# Sheet1.net
KiCad netlist of a schematic drawn in Altium Designer
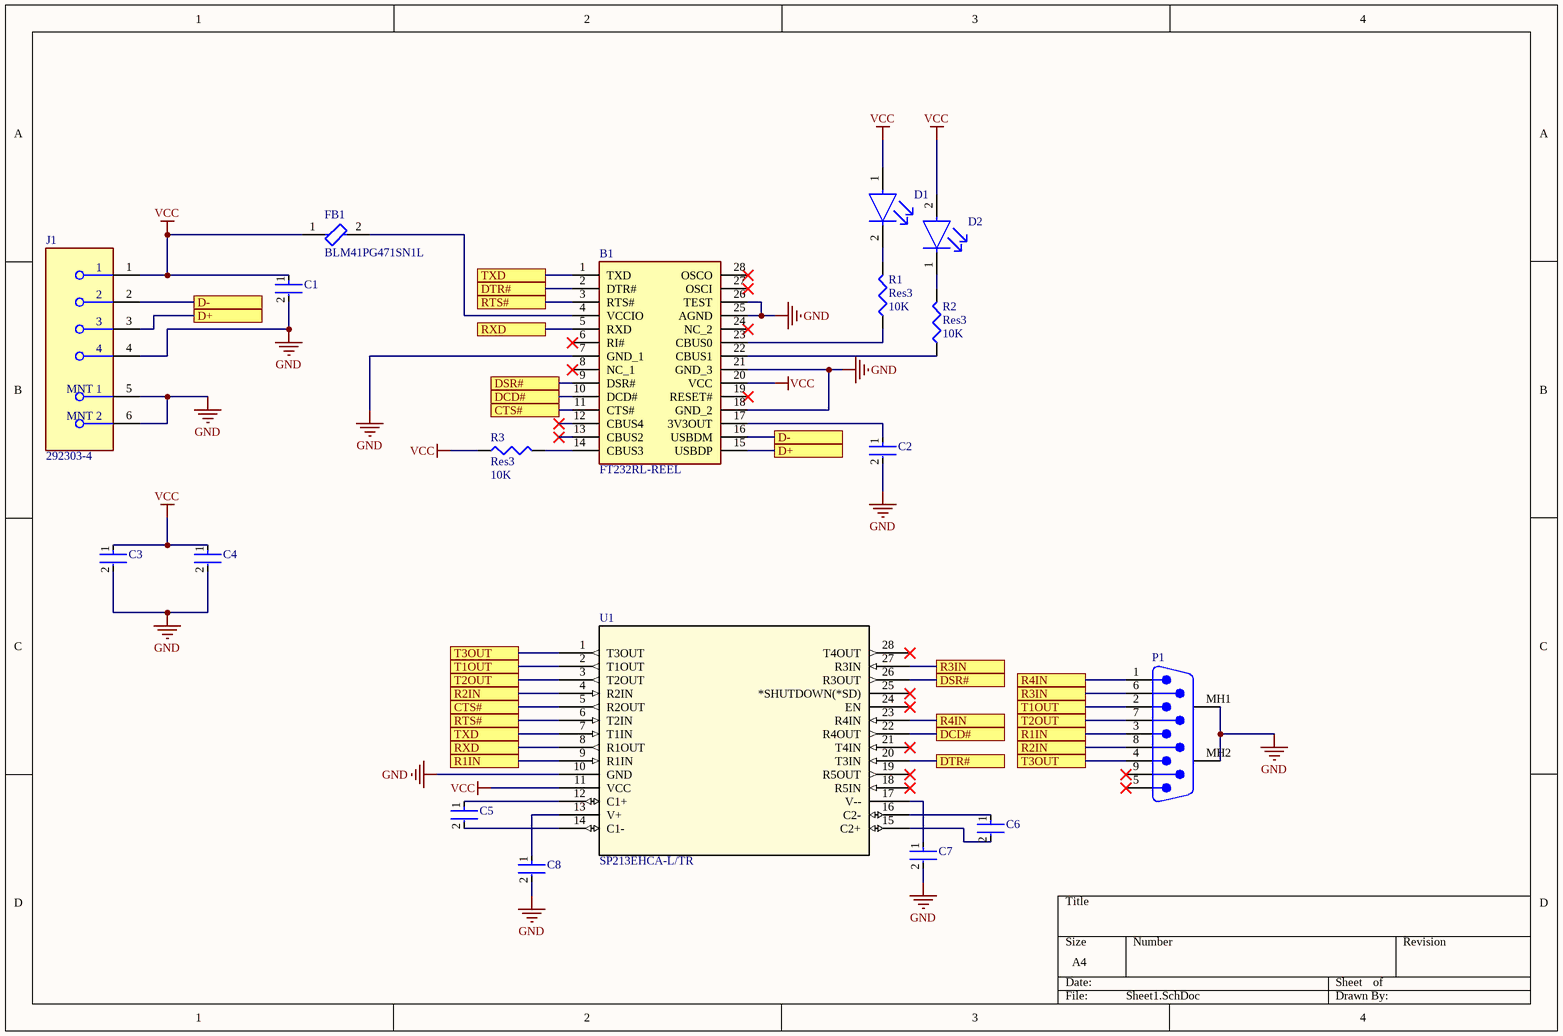
[diagram p0: Sheet1.SchDoc]

(export (version "E")
  (design (tool "Eeschema 10.0.6"))
  (components
    (comp (ref "B1")
      (value "FT232RL-REEL")
      (footprint "SOP65P780X200-28N")
      (description "USB Bridge, USB to UART USB 2.0 UART Interface 28-SSOP")
      (libsource (lib "FT232RL-REEL") (part "FT232RL-REEL"))
    )
    (comp (ref "C1")
      (value "CC0402KPX7R6BB104")
      (footprint "FP-CC0402-MFG")
      (description "CC0402 100 nF X7R 10.00% 10 V")
      (fields
        (field (name "OCTOPART") "https://octopart.com/cc0402kpx7r6bb104-yageo-12885101")
        (field (name "TOLERANCE") "0.1")
      )
      (libsource (lib "Altium Content Vault") (part "11868f565c42a9108669ba33697ecf6"))
    )
    (comp (ref "C2")
      (value "C0603C104M3VAC")
      (footprint "FP-C0603C-CF-MFG")
      (description "C0603 0.10 μF Y5V 30ppm/°C 20.00% 25 V")
      (fields
        (field (name "OCTOPART") "https://octopart.com/c0603c104m3vac-kemet-1325404")
        (field (name "MANUFACTURER") "KEMET")
      )
      (libsource (lib "Altium Content Vault") (part "b4654b650e69147ec39a6b967a45e02"))
    )
    (comp (ref "C3")
      (value "C0603C104M3VAC")
      (footprint "FP-C0603C-CF-MFG")
      (description "C0603 0.10 μF Y5V 30ppm/°C 20.00% 25 V")
      (fields
        (field (name "OCTOPART") "https://octopart.com/c0603c104m3vac-kemet-1325404")
        (field (name "MANUFACTURER") "KEMET")
      )
      (libsource (lib "Altium Content Vault") (part "b4654b650e69147ec39a6b967a45e02"))
    )
    (comp (ref "C4")
      (value "C0603C104M3VAC")
      (footprint "FP-C0603C-CF-MFG")
      (description "C0603 0.10 μF Y5V 30ppm/°C 20.00% 25 V")
      (fields
        (field (name "OCTOPART") "https://octopart.com/c0603c104m3vac-kemet-1325404")
        (field (name "MANUFACTURER") "KEMET")
      )
      (libsource (lib "Altium Content Vault") (part "b4654b650e69147ec39a6b967a45e02"))
    )
    (comp (ref "C5")
      (value "C0603C104M3VAC")
      (footprint "FP-C0603C-CF-MFG")
      (description "C0603 0.10 μF Y5V 30ppm/°C 20.00% 25 V")
      (fields
        (field (name "OCTOPART") "https://octopart.com/c0603c104m3vac-kemet-1325404")
        (field (name "MANUFACTURER") "KEMET")
      )
      (libsource (lib "Altium Content Vault") (part "b4654b650e69147ec39a6b967a45e02"))
    )
    (comp (ref "C6")
      (value "C0603C104M3VAC")
      (footprint "FP-C0603C-CF-MFG")
      (description "C0603 0.10 μF Y5V 30ppm/°C 20.00% 25 V")
      (fields
        (field (name "OCTOPART") "https://octopart.com/c0603c104m3vac-kemet-1325404")
        (field (name "MANUFACTURER") "KEMET")
      )
      (libsource (lib "Altium Content Vault") (part "b4654b650e69147ec39a6b967a45e02"))
    )
    (comp (ref "C7")
      (value "C0603C104M3VAC")
      (footprint "FP-C0603C-CF-MFG")
      (description "C0603 0.10 μF Y5V 30ppm/°C 20.00% 25 V")
      (fields
        (field (name "OCTOPART") "https://octopart.com/c0603c104m3vac-kemet-1325404")
        (field (name "MANUFACTURER") "KEMET")
      )
      (libsource (lib "Altium Content Vault") (part "b4654b650e69147ec39a6b967a45e02"))
    )
    (comp (ref "C8")
      (value "C0603C104M3VAC")
      (footprint "FP-C0603C-CF-MFG")
      (description "C0603 0.10 μF Y5V 30ppm/°C 20.00% 25 V")
      (fields
        (field (name "OCTOPART") "https://octopart.com/c0603c104m3vac-kemet-1325404")
        (field (name "MANUFACTURER") "KEMET")
      )
      (libsource (lib "Altium Content Vault") (part "b4654b650e69147ec39a6b967a45e02"))
    )
    (comp (ref "D1")
      (value "AP2012EC")
      (footprint "FP-AP2012EC-MFG")
      (description "LED RED CLEAR SMD")
      (libsource (lib "Altium Content Vault") (part "ab1c01a81903e929fc6c44469aada92"))
    )
    (comp (ref "D2")
      (value "APT1608LZGCK")
      (footprint "FP-APT1608LZGCK-MFG")
      (description "LED GREEN CLEAR 2SMD")
      (libsource (lib "Altium Content Vault") (part "8706943c75ba83719d021d2fdc84c58"))
    )
    (comp (ref "FB1")
      (value "BLM41PG471SN1L")
      (footprint "FP-BLM41-0_2-a1_2-IPC_B")
      (description "Ferrite Bead, 1806, 470Ω @ 100MHz, 25%, 0.05Ω, 2A")
      (fields (field (name "TOLERANCE") "25%"))
      (libsource (lib "Altium Content Vault") (part "5f30dd21d616792df468990f7003faa"))
    )
    (comp (ref "J1")
      (value "292303-4")
      (footprint "FP-292303-4-MFG")
      (description "CONN RCPT USB2.0 TYPEA 4POS R/A")
      (fields
        (field (name "MANUFACTURER") "TE Connectivity")
        (field (name "OCTOPART") "https://octopart.com/292303-4-te+connectivity-39545343")
      )
      (libsource (lib "Altium Content Vault") (part "79e6714efa0bb2f851c24b2688127c9"))
    )
    (comp (ref "P1")
      (value "5747840-3")
      (footprint "TECO-5747840-3_V")
      (fields (field (name "MANUFACTURER") "TE Connectivity"))
      (libsource (lib "Altium Content Vault") (part "CN-2S-2M-D9"))
    )
    (comp (ref "R1")
      (value "Res3")
      (footprint "J1-0603")
      (description "Resistor")
      (fields (field (name "ALTIUM_VALUE") "10K") (field (name "PUBLISHER") "Altium Limited"))
      (libsource (lib "Miscellaneous Devices") (part "Res3"))
    )
    (comp (ref "R2")
      (value "Res3")
      (footprint "J1-0603")
      (description "Resistor")
      (fields (field (name "ALTIUM_VALUE") "10K") (field (name "PUBLISHER") "Altium Limited"))
      (libsource (lib "Miscellaneous Devices") (part "Res3"))
    )
    (comp (ref "R3")
      (value "Res3")
      (footprint "J1-0603")
      (description "Resistor")
      (fields (field (name "ALTIUM_VALUE") "10K") (field (name "PUBLISHER") "Altium Limited"))
      (libsource (lib "Miscellaneous Devices") (part "Res3"))
    )
    (comp (ref "U1")
      (value "SP213EHCA-L/TR")
      (footprint "SSOP-28")
      (description "No Description Available")
      (fields (field (name "COPYRIGHT") "Copyright (C) 2025 Ultra Librarian. All rights reserved."))
      (libsource (lib "SP213EHCA-LTR") (part "SP213EHCA-LTR"))
    )
  )
  (nets
    (net (code "1") (name "/CTS#") (class "Default")
      (node (ref "B1") (pin "11") (pinfunction "CTS#_11") (pintype "passive"))
      (node (ref "U1") (pin "5") (pinfunction "R2OUT_5") (pintype "output"))
    )
    (net (code "2") (name "/D+") (class "Default")
      (node (ref "B1") (pin "15") (pinfunction "USBDP_15") (pintype "passive"))
      (node (ref "J1") (pin "3") (pinfunction "3_3") (pintype "passive"))
    )
    (net (code "3") (name "/D-") (class "Default")
      (node (ref "B1") (pin "16") (pinfunction "USBDM_16") (pintype "passive"))
      (node (ref "J1") (pin "2") (pinfunction "2_2") (pintype "passive"))
    )
    (net (code "4") (name "/DCD#") (class "Default")
      (node (ref "B1") (pin "10") (pinfunction "DCD#_10") (pintype "passive"))
      (node (ref "U1") (pin "22") (pinfunction "R4OUT_22") (pintype "output"))
    )
    (net (code "5") (name "/DSR#") (class "Default")
      (node (ref "B1") (pin "9") (pinfunction "DSR#_9") (pintype "passive"))
      (node (ref "U1") (pin "26") (pinfunction "R3OUT_26") (pintype "output"))
    )
    (net (code "6") (name "/DTR#") (class "Default")
      (node (ref "B1") (pin "2") (pinfunction "DTR#_2") (pintype "passive"))
      (node (ref "U1") (pin "20") (pinfunction "T3IN_20") (pintype "input"))
    )
    (net (code "7") (name "/R1IN") (class "Default")
      (node (ref "P1") (pin "3") (pinfunction "3_3") (pintype "passive"))
      (node (ref "U1") (pin "9") (pinfunction "R1IN_9") (pintype "input"))
    )
    (net (code "8") (name "/R2IN") (class "Default")
      (node (ref "P1") (pin "8") (pinfunction "8_8") (pintype "passive"))
      (node (ref "U1") (pin "4") (pinfunction "R2IN_4") (pintype "input"))
    )
    (net (code "9") (name "/R3IN") (class "Default")
      (node (ref "P1") (pin "6") (pinfunction "6_6") (pintype "passive"))
      (node (ref "U1") (pin "27") (pinfunction "R3IN_27") (pintype "input"))
    )
    (net (code "10") (name "/R4IN") (class "Default")
      (node (ref "P1") (pin "1") (pinfunction "1_1") (pintype "passive"))
      (node (ref "U1") (pin "23") (pinfunction "R4IN_23") (pintype "input"))
    )
    (net (code "11") (name "/RTS#") (class "Default")
      (node (ref "B1") (pin "3") (pinfunction "RTS#_3") (pintype "passive"))
      (node (ref "U1") (pin "6") (pinfunction "T2IN_6") (pintype "input"))
    )
    (net (code "12") (name "/RXD") (class "Default")
      (node (ref "B1") (pin "5") (pinfunction "RXD_5") (pintype "passive"))
      (node (ref "U1") (pin "8") (pinfunction "R1OUT_8") (pintype "output"))
    )
    (net (code "13") (name "/T1OUT") (class "Default")
      (node (ref "P1") (pin "2") (pinfunction "2_2") (pintype "passive"))
      (node (ref "U1") (pin "2") (pinfunction "T1OUT_2") (pintype "output"))
    )
    (net (code "14") (name "/T2OUT") (class "Default")
      (node (ref "P1") (pin "7") (pinfunction "7_7") (pintype "passive"))
      (node (ref "U1") (pin "3") (pinfunction "T2OUT_3") (pintype "output"))
    )
    (net (code "15") (name "/T3OUT") (class "Default")
      (node (ref "P1") (pin "4") (pinfunction "4_4") (pintype "passive"))
      (node (ref "U1") (pin "1") (pinfunction "T3OUT_1") (pintype "output"))
    )
    (net (code "16") (name "/TXD") (class "Default")
      (node (ref "B1") (pin "1") (pinfunction "TXD_1") (pintype "passive"))
      (node (ref "U1") (pin "7") (pinfunction "T1IN_7") (pintype "input"))
    )
    (net (code "17") (name "GND") (class "Default")
      (node (ref "B1") (pin "18") (pinfunction "GND_2_18") (pintype "passive"))
      (node (ref "B1") (pin "21") (pinfunction "GND_3_21") (pintype "passive"))
      (node (ref "B1") (pin "25") (pinfunction "AGND_25") (pintype "passive"))
      (node (ref "B1") (pin "26") (pinfunction "TEST_26") (pintype "passive"))
      (node (ref "B1") (pin "7") (pinfunction "GND_1_7") (pintype "passive"))
      (node (ref "C1") (pin "2") (pinfunction "2_2") (pintype "passive"))
      (node (ref "C2") (pin "2") (pinfunction "2_2") (pintype "passive"))
      (node (ref "C3") (pin "2") (pinfunction "2_2") (pintype "passive"))
      (node (ref "C4") (pin "2") (pinfunction "2_2") (pintype "passive"))
      (node (ref "C7") (pin "2") (pinfunction "2_2") (pintype "passive"))
      (node (ref "C8") (pin "2") (pinfunction "2_2") (pintype "passive"))
      (node (ref "J1") (pin "4") (pinfunction "4_4") (pintype "passive"))
      (node (ref "J1") (pin "5") (pinfunction "MNT_1_5") (pintype "passive"))
      (node (ref "J1") (pin "6") (pinfunction "MNT_2_6") (pintype "passive"))
      (node (ref "P1") (pin "MH1") (pinfunction "MH1_MH1") (pintype "passive"))
      (node (ref "P1") (pin "MH2") (pinfunction "MH2_MH2") (pintype "passive"))
      (node (ref "U1") (pin "10") (pinfunction "GND_10") (pintype "power_in"))
    )
    (net (code "18") (name "Net-(B1-3V3OUT)") (class "Default")
      (node (ref "B1") (pin "17") (pinfunction "3V3OUT_17") (pintype "passive"))
      (node (ref "C2") (pin "1") (pinfunction "1_1") (pintype "passive"))
    )
    (net (code "19") (name "Net-(B1-CBUS0)") (class "Default")
      (node (ref "B1") (pin "23") (pinfunction "CBUS0_23") (pintype "passive"))
      (node (ref "R1") (pin "1") (pinfunction "1_1") (pintype "passive"))
    )
    (net (code "20") (name "Net-(B1-CBUS1)") (class "Default")
      (node (ref "B1") (pin "22") (pinfunction "CBUS1_22") (pintype "passive"))
      (node (ref "R2") (pin "1") (pinfunction "1_1") (pintype "passive"))
    )
    (net (code "21") (name "Net-(B1-CBUS3)") (class "Default")
      (node (ref "B1") (pin "14") (pinfunction "CBUS3_14") (pintype "passive"))
      (node (ref "R3") (pin "2") (pinfunction "2_2") (pintype "passive"))
    )
    (net (code "22") (name "Net-(B1-VCCIO)") (class "Default")
      (node (ref "B1") (pin "4") (pinfunction "VCCIO_4") (pintype "passive"))
      (node (ref "FB1") (pin "2") (pinfunction "2_2") (pintype "passive"))
    )
    (net (code "23") (name "Net-(D1-C)") (class "Default")
      (node (ref "D1") (pin "2") (pinfunction "C_2") (pintype "passive"))
      (node (ref "R1") (pin "2") (pinfunction "2_2") (pintype "passive"))
    )
    (net (code "24") (name "Net-(D2-C)") (class "Default")
      (node (ref "D2") (pin "1") (pinfunction "C_1") (pintype "passive"))
      (node (ref "R2") (pin "2") (pinfunction "2_2") (pintype "passive"))
    )
    (net (code "25") (name "Net-(U1-C1+)") (class "Default")
      (node (ref "C5") (pin "1") (pinfunction "1_1") (pintype "passive"))
      (node (ref "U1") (pin "12") (pinfunction "C1+_12") (pintype "bidirectional"))
    )
    (net (code "26") (name "Net-(U1-C1-)") (class "Default")
      (node (ref "C5") (pin "2") (pinfunction "2_2") (pintype "passive"))
      (node (ref "U1") (pin "14") (pinfunction "C1-_14") (pintype "bidirectional"))
    )
    (net (code "27") (name "Net-(U1-C2+)") (class "Default")
      (node (ref "C6") (pin "2") (pinfunction "2_2") (pintype "passive"))
      (node (ref "U1") (pin "15") (pinfunction "C2+_15") (pintype "bidirectional"))
    )
    (net (code "28") (name "Net-(U1-C2-)") (class "Default")
      (node (ref "C6") (pin "1") (pinfunction "1_1") (pintype "passive"))
      (node (ref "U1") (pin "16") (pinfunction "C2-_16") (pintype "bidirectional"))
    )
    (net (code "29") (name "Net-(U1-V+)") (class "Default")
      (node (ref "C8") (pin "1") (pinfunction "1_1") (pintype "passive"))
      (node (ref "U1") (pin "13") (pinfunction "V+_13") (pintype "power_in"))
    )
    (net (code "30") (name "Net-(U1-V--)") (class "Default")
      (node (ref "C7") (pin "1") (pinfunction "1_1") (pintype "passive"))
      (node (ref "U1") (pin "17") (pinfunction "V--_17") (pintype "power_in"))
    )
    (net (code "31") (name "VCC") (class "Default")
      (node (ref "B1") (pin "20") (pinfunction "VCC_20") (pintype "passive"))
      (node (ref "C1") (pin "1") (pinfunction "1_1") (pintype "passive"))
      (node (ref "C3") (pin "1") (pinfunction "1_1") (pintype "passive"))
      (node (ref "C4") (pin "1") (pinfunction "1_1") (pintype "passive"))
      (node (ref "D1") (pin "1") (pinfunction "A_1") (pintype "passive"))
      (node (ref "D2") (pin "2") (pinfunction "A_2") (pintype "passive"))
      (node (ref "FB1") (pin "1") (pinfunction "1_1") (pintype "passive"))
      (node (ref "J1") (pin "1") (pinfunction "1_1") (pintype "passive"))
      (node (ref "R3") (pin "1") (pinfunction "1_1") (pintype "passive"))
      (node (ref "U1") (pin "11") (pinfunction "VCC_11") (pintype "power_in"))
    )
    (net (code "32") (name "unconnected-(B1-CBUS2-Pad13)") (class "Default")
      (node (ref "B1") (pin "13") (pinfunction "CBUS2_13") (pintype "passive+no_connect"))
    )
    (net (code "33") (name "unconnected-(B1-CBUS4-Pad12)") (class "Default")
      (node (ref "B1") (pin "12") (pinfunction "CBUS4_12") (pintype "passive+no_connect"))
    )
    (net (code "34") (name "unconnected-(B1-NC_1-Pad8)") (class "Default")
      (node (ref "B1") (pin "8") (pinfunction "NC_1_8") (pintype "passive+no_connect"))
    )
    (net (code "35") (name "unconnected-(B1-NC_2-Pad24)") (class "Default")
      (node (ref "B1") (pin "24") (pinfunction "NC_2_24") (pintype "passive+no_connect"))
    )
    (net (code "36") (name "unconnected-(B1-OSCI-Pad27)") (class "Default")
      (node (ref "B1") (pin "27") (pinfunction "OSCI_27") (pintype "passive+no_connect"))
    )
    (net (code "37") (name "unconnected-(B1-OSCO-Pad28)") (class "Default")
      (node (ref "B1") (pin "28") (pinfunction "OSCO_28") (pintype "passive+no_connect"))
    )
    (net (code "38") (name "unconnected-(B1-RESET#-Pad19)") (class "Default")
      (node (ref "B1") (pin "19") (pinfunction "RESET#_19") (pintype "passive+no_connect"))
    )
    (net (code "39") (name "unconnected-(B1-RI#-Pad6)") (class "Default")
      (node (ref "B1") (pin "6") (pinfunction "RI#_6") (pintype "passive+no_connect"))
    )
    (net (code "40") (name "unconnected-(P1-Pad5)") (class "Default")
      (node (ref "P1") (pin "5") (pinfunction "5_5") (pintype "passive+no_connect"))
    )
    (net (code "41") (name "unconnected-(P1-Pad9)") (class "Default")
      (node (ref "P1") (pin "9") (pinfunction "9_9") (pintype "passive+no_connect"))
    )
    (net (code "42") (name "unconnected-(U1-*SHUTDOWN(*SD)-Pad25)") (class "Default")
      (node (ref "U1") (pin "25") (pinfunction "*SHUTDOWN(*SD)_25") (pintype "passive+no_connect"))
    )
    (net (code "43") (name "unconnected-(U1-EN-Pad24)") (class "Default")
      (node (ref "U1") (pin "24") (pinfunction "EN_24") (pintype "passive+no_connect"))
    )
    (net (code "44") (name "unconnected-(U1-R5IN-Pad18)") (class "Default")
      (node (ref "U1") (pin "18") (pinfunction "R5IN_18") (pintype "input+no_connect"))
    )
    (net (code "45") (name "unconnected-(U1-R5OUT-Pad19)") (class "Default")
      (node (ref "U1") (pin "19") (pinfunction "R5OUT_19") (pintype "output+no_connect"))
    )
    (net (code "46") (name "unconnected-(U1-T4IN-Pad21)") (class "Default")
      (node (ref "U1") (pin "21") (pinfunction "T4IN_21") (pintype "input+no_connect"))
    )
    (net (code "47") (name "unconnected-(U1-T4OUT-Pad28)") (class "Default")
      (node (ref "U1") (pin "28") (pinfunction "T4OUT_28") (pintype "output+no_connect"))
    )
  )
)
